# BATT_FLEX12.net
KiCad netlist of a schematic drawn in EAGLE
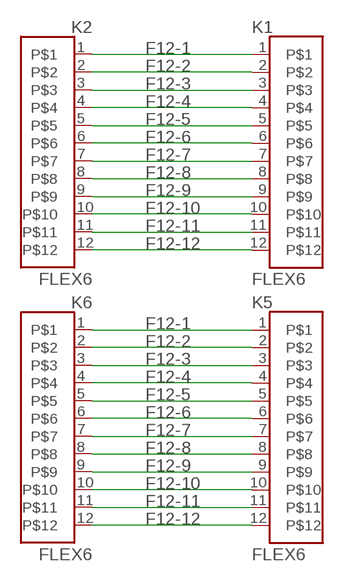
[diagram p0: schematic, sheet 1]

(export (version "E")
  (design (tool "Eeschema 10.0.6"))
  (components
    (comp (ref "K1")
      (value "FLEX6")
      (footprint "eagle-import:FLEX6")
      (libsource (lib "eagle-import") (part "FLEX6"))
    )
    (comp (ref "K2")
      (value "FLEX6")
      (footprint "eagle-import:FLEX6")
      (libsource (lib "eagle-import") (part "FLEX6"))
    )
    (comp (ref "K5")
      (value "FLEX6")
      (footprint "eagle-import:FLEX6")
      (libsource (lib "eagle-import") (part "FLEX6"))
    )
    (comp (ref "K6")
      (value "FLEX6")
      (footprint "eagle-import:FLEX6")
      (libsource (lib "eagle-import") (part "FLEX6"))
    )
  )
  (nets
    (net (code "1") (name "/F12-1") (class "Default")
      (node (ref "K1") (pin "1") (pinfunction "P$1_1") (pintype "bidirectional"))
      (node (ref "K2") (pin "1") (pinfunction "P$1_1") (pintype "bidirectional"))
      (node (ref "K5") (pin "1") (pinfunction "P$1_1") (pintype "bidirectional"))
      (node (ref "K6") (pin "1") (pinfunction "P$1_1") (pintype "bidirectional"))
    )
    (net (code "2") (name "/F12-2") (class "Default")
      (node (ref "K1") (pin "2") (pinfunction "P$2_2") (pintype "bidirectional"))
      (node (ref "K2") (pin "2") (pinfunction "P$2_2") (pintype "bidirectional"))
      (node (ref "K5") (pin "2") (pinfunction "P$2_2") (pintype "bidirectional"))
      (node (ref "K6") (pin "2") (pinfunction "P$2_2") (pintype "bidirectional"))
    )
    (net (code "3") (name "/F12-3") (class "Default")
      (node (ref "K1") (pin "3") (pinfunction "P$3_3") (pintype "bidirectional"))
      (node (ref "K2") (pin "3") (pinfunction "P$3_3") (pintype "bidirectional"))
      (node (ref "K5") (pin "3") (pinfunction "P$3_3") (pintype "bidirectional"))
      (node (ref "K6") (pin "3") (pinfunction "P$3_3") (pintype "bidirectional"))
    )
    (net (code "4") (name "/F12-4") (class "Default")
      (node (ref "K1") (pin "4") (pinfunction "P$4_4") (pintype "bidirectional"))
      (node (ref "K2") (pin "4") (pinfunction "P$4_4") (pintype "bidirectional"))
      (node (ref "K5") (pin "4") (pinfunction "P$4_4") (pintype "bidirectional"))
      (node (ref "K6") (pin "4") (pinfunction "P$4_4") (pintype "bidirectional"))
    )
    (net (code "5") (name "/F12-5") (class "Default")
      (node (ref "K1") (pin "5") (pinfunction "P$5_5") (pintype "bidirectional"))
      (node (ref "K2") (pin "5") (pinfunction "P$5_5") (pintype "bidirectional"))
      (node (ref "K5") (pin "5") (pinfunction "P$5_5") (pintype "bidirectional"))
      (node (ref "K6") (pin "5") (pinfunction "P$5_5") (pintype "bidirectional"))
    )
    (net (code "6") (name "/F12-6") (class "Default")
      (node (ref "K1") (pin "6") (pinfunction "P$6_6") (pintype "bidirectional"))
      (node (ref "K2") (pin "6") (pinfunction "P$6_6") (pintype "bidirectional"))
      (node (ref "K5") (pin "6") (pinfunction "P$6_6") (pintype "bidirectional"))
      (node (ref "K6") (pin "6") (pinfunction "P$6_6") (pintype "bidirectional"))
    )
    (net (code "7") (name "/F12-7") (class "Default")
      (node (ref "K1") (pin "7") (pinfunction "P$7_7") (pintype "bidirectional"))
      (node (ref "K2") (pin "7") (pinfunction "P$7_7") (pintype "bidirectional"))
      (node (ref "K5") (pin "7") (pinfunction "P$7_7") (pintype "bidirectional"))
      (node (ref "K6") (pin "7") (pinfunction "P$7_7") (pintype "bidirectional"))
    )
    (net (code "8") (name "/F12-8") (class "Default")
      (node (ref "K1") (pin "8") (pinfunction "P$8_8") (pintype "bidirectional"))
      (node (ref "K2") (pin "8") (pinfunction "P$8_8") (pintype "bidirectional"))
      (node (ref "K5") (pin "8") (pinfunction "P$8_8") (pintype "bidirectional"))
      (node (ref "K6") (pin "8") (pinfunction "P$8_8") (pintype "bidirectional"))
    )
    (net (code "9") (name "/F12-9") (class "Default")
      (node (ref "K1") (pin "9") (pinfunction "P$9_9") (pintype "bidirectional"))
      (node (ref "K2") (pin "9") (pinfunction "P$9_9") (pintype "bidirectional"))
      (node (ref "K5") (pin "9") (pinfunction "P$9_9") (pintype "bidirectional"))
      (node (ref "K6") (pin "9") (pinfunction "P$9_9") (pintype "bidirectional"))
    )
    (net (code "10") (name "/F12-10") (class "Default")
      (node (ref "K1") (pin "10") (pinfunction "P$10_10") (pintype "bidirectional"))
      (node (ref "K2") (pin "10") (pinfunction "P$10_10") (pintype "bidirectional"))
      (node (ref "K5") (pin "10") (pinfunction "P$10_10") (pintype "bidirectional"))
      (node (ref "K6") (pin "10") (pinfunction "P$10_10") (pintype "bidirectional"))
    )
    (net (code "11") (name "/F12-11") (class "Default")
      (node (ref "K1") (pin "11") (pinfunction "P$11_11") (pintype "bidirectional"))
      (node (ref "K2") (pin "11") (pinfunction "P$11_11") (pintype "bidirectional"))
      (node (ref "K5") (pin "11") (pinfunction "P$11_11") (pintype "bidirectional"))
      (node (ref "K6") (pin "11") (pinfunction "P$11_11") (pintype "bidirectional"))
    )
    (net (code "12") (name "/F12-12") (class "Default")
      (node (ref "K1") (pin "12") (pinfunction "P$12_12") (pintype "bidirectional"))
      (node (ref "K2") (pin "12") (pinfunction "P$12_12") (pintype "bidirectional"))
      (node (ref "K5") (pin "12") (pinfunction "P$12_12") (pintype "bidirectional"))
      (node (ref "K6") (pin "12") (pinfunction "P$12_12") (pintype "bidirectional"))
    )
  )
)
